# ai_cricket.net
KiCad netlist of a schematic drawn in EAGLE
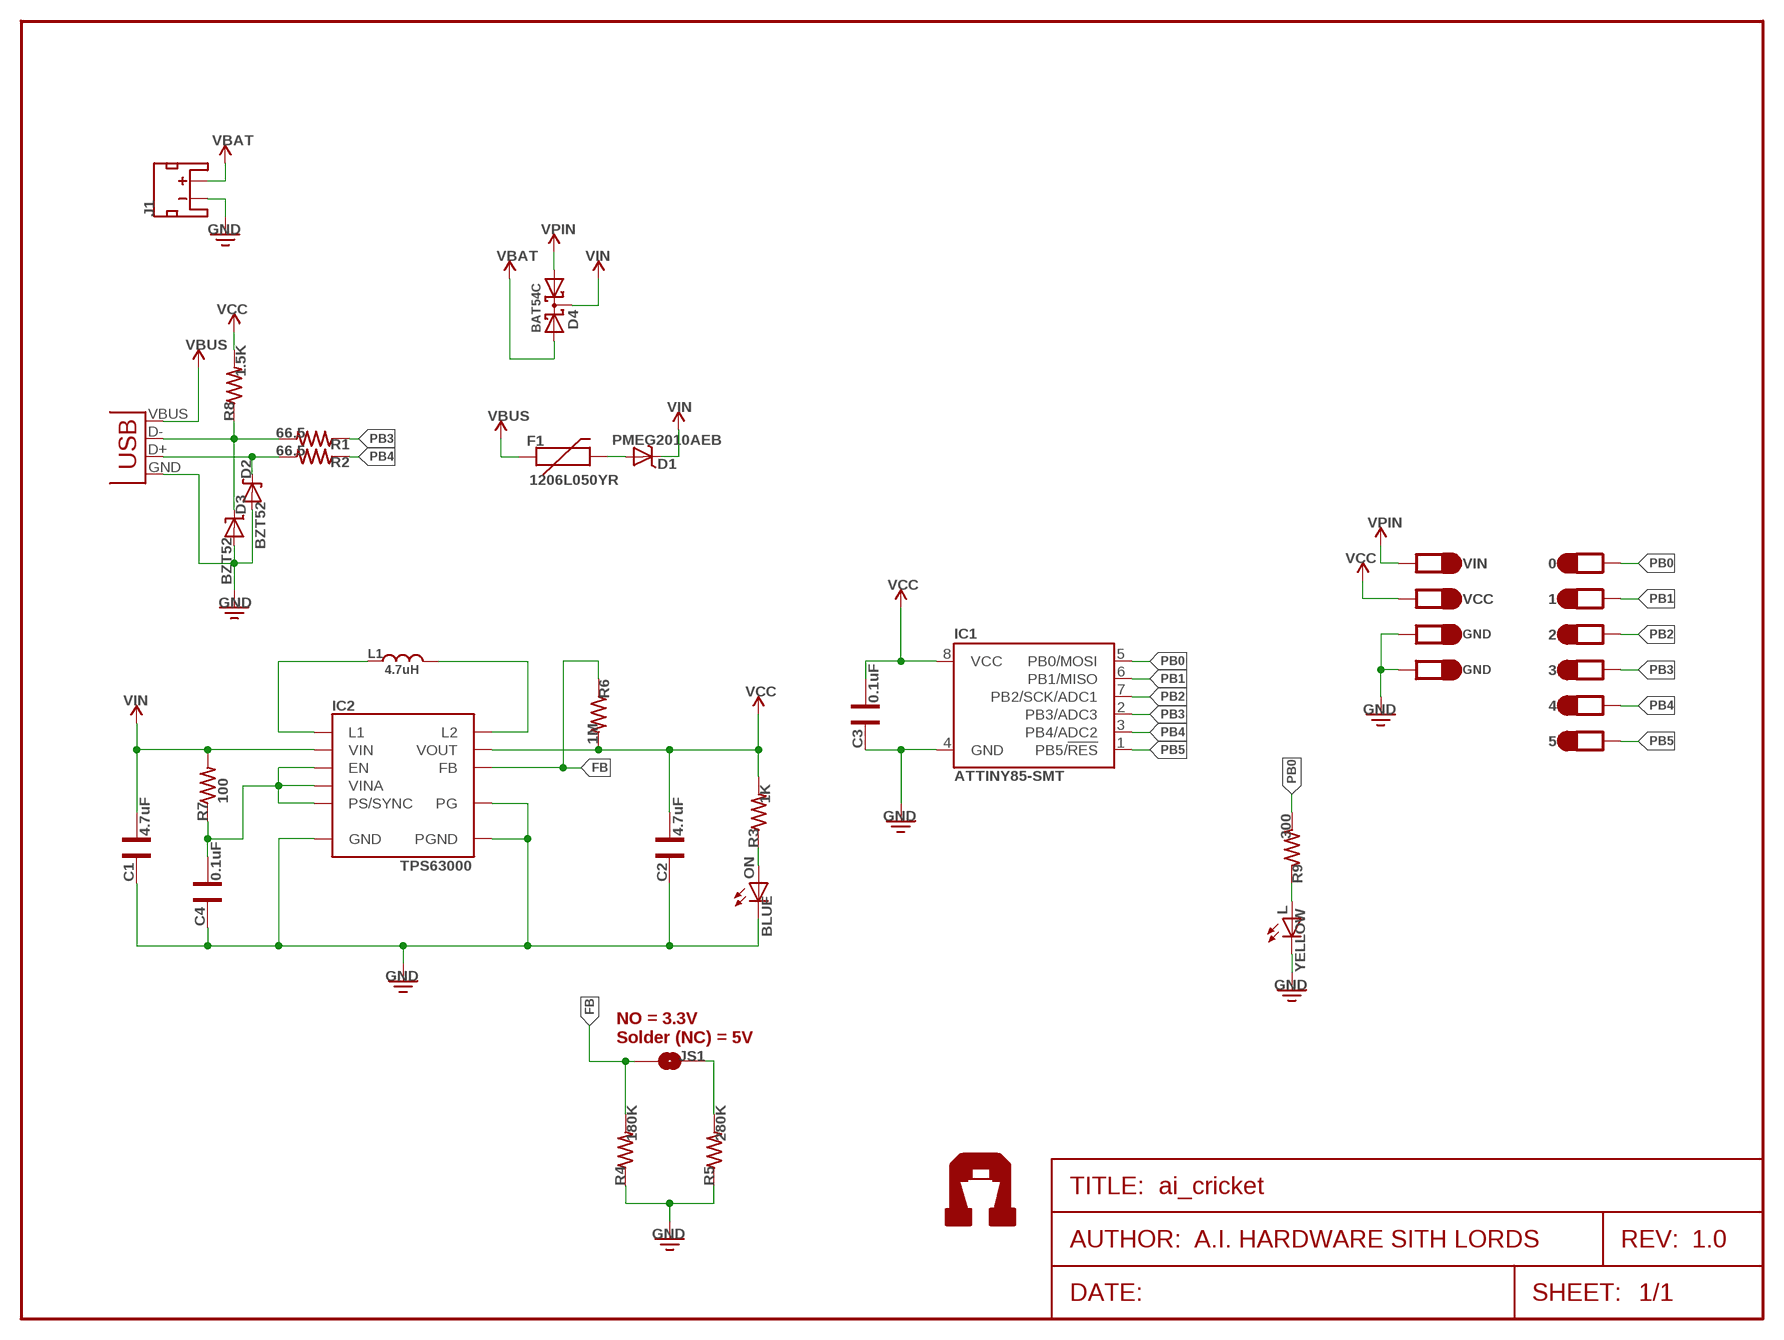
[diagram p0: schematic, sheet 1]

(export (version "E")
  (design (tool "Eeschema 10.0.6"))
  (components
    (comp (ref "0")
      (value "1X01-PETAL")
      (footprint "eagle-import:1X01-PETAL")
      (libsource (lib "eagle-import") (part "1X01-PETAL"))
    )
    (comp (ref "1")
      (value "1X01-PETAL")
      (footprint "eagle-import:1X01-PETAL")
      (libsource (lib "eagle-import") (part "1X01-PETAL"))
    )
    (comp (ref "2")
      (value "1X01-PETAL")
      (footprint "eagle-import:1X01-PETAL")
      (libsource (lib "eagle-import") (part "1X01-PETAL"))
    )
    (comp (ref "3")
      (value "1X01-PETAL")
      (footprint "eagle-import:1X01-PETAL")
      (libsource (lib "eagle-import") (part "1X01-PETAL"))
    )
    (comp (ref "4")
      (value "1X01-PETAL")
      (footprint "eagle-import:1X01-PETAL")
      (libsource (lib "eagle-import") (part "1X01-PETAL"))
    )
    (comp (ref "5")
      (value "1X01-PETAL")
      (footprint "eagle-import:1X01-PETAL")
      (libsource (lib "eagle-import") (part "1X01-PETAL"))
    )
    (comp (ref "C1")
      (value "4.7uF")
      (footprint "eagle-import:CAP-0402")
      (libsource (lib "eagle-import") (part "CAP0402"))
    )
    (comp (ref "C2")
      (value "4.7uF")
      (footprint "eagle-import:CAP-0402")
      (libsource (lib "eagle-import") (part "CAP0402"))
    )
    (comp (ref "C3")
      (value "0.1uF")
      (footprint "eagle-import:CAP-0402")
      (libsource (lib "eagle-import") (part "CAP0402"))
    )
    (comp (ref "C4")
      (value "0.1uF")
      (footprint "eagle-import:CAP-0402")
      (libsource (lib "eagle-import") (part "CAP0402"))
    )
    (comp (ref "D1")
      (value "PMEG2010AEB")
      (footprint "eagle-import:SOD-523")
      (libsource (lib "eagle-import") (part "DIODE-SCHOTTKYSOD-523"))
    )
    (comp (ref "D2")
      (value "BZT52")
      (footprint "eagle-import:SOD-323")
      (libsource (lib "eagle-import") (part "DIODE-ZENER-BZT52"))
    )
    (comp (ref "D3")
      (value "BZT52")
      (footprint "eagle-import:SOD-323")
      (libsource (lib "eagle-import") (part "DIODE-ZENER-BZT52"))
    )
    (comp (ref "D4")
      (value "BAT54C")
      (footprint "eagle-import:SOT-23")
      (libsource (lib "eagle-import") (part "BAT54C"))
    )
    (comp (ref "F1")
      (value "1206L050YR")
      (footprint "eagle-import:PTC-1206")
      (libsource (lib "eagle-import") (part "PTCSMD"))
    )
    (comp (ref "GND7")
      (value "1X01-PETAL")
      (footprint "eagle-import:1X01-PETAL")
      (libsource (lib "eagle-import") (part "1X01-PETAL"))
    )
    (comp (ref "GND8")
      (value "1X01-PETAL")
      (footprint "eagle-import:1X01-PETAL")
      (libsource (lib "eagle-import") (part "1X01-PETAL"))
    )
    (comp (ref "IC1")
      (value "ATTINY85-SMT")
      (footprint "eagle-import:S008-EIAJ")
      (libsource (lib "eagle-import") (part "ATTINY85-SMT"))
    )
    (comp (ref "IC2")
      (value "TPS63000")
      (footprint "eagle-import:10-VFDFN")
      (libsource (lib "eagle-import") (part "TPS63000"))
    )
    (comp (ref "J1")
      (value "JST-2-MALE")
      (footprint "eagle-import:JST-2-SMD")
      (libsource (lib "eagle-import") (part "JST-2-MALE"))
    )
    (comp (ref "JS1")
      (value "1X02-SJ-NO")
      (footprint "eagle-import:1X02-SJ-NO")
      (libsource (lib "eagle-import") (part "1X02-SJ-NO"))
    )
    (comp (ref "L")
      (value "YELLOW")
      (footprint "eagle-import:LED-0603")
      (libsource (lib "eagle-import") (part "LED0603"))
    )
    (comp (ref "L1")
      (value "4.7uH")
      (footprint "eagle-import:IND-0603")
      (libsource (lib "eagle-import") (part "IND0603"))
    )
    (comp (ref "ON")
      (value "BLUE")
      (footprint "eagle-import:LED-0603")
      (libsource (lib "eagle-import") (part "LED0603"))
    )
    (comp (ref "R1")
      (value "66.5")
      (footprint "eagle-import:RES-0402")
      (libsource (lib "eagle-import") (part "RES0402"))
    )
    (comp (ref "R2")
      (value "66.5")
      (footprint "eagle-import:RES-0402")
      (libsource (lib "eagle-import") (part "RES0402"))
    )
    (comp (ref "R3")
      (value "1K")
      (footprint "eagle-import:RES-0402")
      (libsource (lib "eagle-import") (part "RES0402"))
    )
    (comp (ref "R4")
      (value "180K")
      (footprint "eagle-import:RES-0402")
      (libsource (lib "eagle-import") (part "RES0402"))
    )
    (comp (ref "R5")
      (value "280K")
      (footprint "eagle-import:RES-0402")
      (libsource (lib "eagle-import") (part "RES0402"))
    )
    (comp (ref "R6")
      (value "1M")
      (footprint "eagle-import:RES-0402")
      (libsource (lib "eagle-import") (part "RES0402"))
    )
    (comp (ref "R7")
      (value "100")
      (footprint "eagle-import:RES-0402")
      (libsource (lib "eagle-import") (part "RES0402"))
    )
    (comp (ref "R8")
      (value "1.5K")
      (footprint "eagle-import:RES-0402")
      (libsource (lib "eagle-import") (part "RES0402"))
    )
    (comp (ref "R9")
      (value "300")
      (footprint "eagle-import:RES-0402")
      (libsource (lib "eagle-import") (part "RES0402"))
    )
    (comp (ref "U$14")
      (value "AI-LOGOXS")
      (footprint "eagle-import:AI-LOGO-XS")
      (libsource (lib "eagle-import") (part "AI-LOGOXS"))
    )
    (comp (ref "USB1")
      (value "USBMICROB-TH")
      (footprint "eagle-import:USB-MICROB-TH")
      (libsource (lib "eagle-import") (part "USBMICROB-TH"))
    )
    (comp (ref "VCC")
      (value "1X01-PETAL")
      (footprint "eagle-import:1X01-PETAL")
      (libsource (lib "eagle-import") (part "1X01-PETAL"))
    )
    (comp (ref "VIN")
      (value "1X01-PETAL")
      (footprint "eagle-import:1X01-PETAL")
      (libsource (lib "eagle-import") (part "1X01-PETAL"))
    )
  )
  (nets
    (net (code "1") (name "FB") (class "Default")
      (node (ref "IC2") (pin "10") (pinfunction "FB_10") (pintype "input"))
      (node (ref "JS1") (pin "1") (pinfunction "1_1") (pintype "passive"))
      (node (ref "R4") (pin "2") (pinfunction "2_2") (pintype "passive"))
      (node (ref "R6") (pin "1") (pinfunction "1_1") (pintype "passive"))
    )
    (net (code "2") (name "GND") (class "Default")
      (node (ref "C1") (pin "2") (pinfunction "2_2") (pintype "passive"))
      (node (ref "C2") (pin "2") (pinfunction "2_2") (pintype "passive"))
      (node (ref "C3") (pin "2") (pinfunction "2_2") (pintype "passive"))
      (node (ref "C4") (pin "2") (pinfunction "2_2") (pintype "passive"))
      (node (ref "D2") (pin "A") (pinfunction "A_A") (pintype "passive"))
      (node (ref "D3") (pin "A") (pinfunction "A_A") (pintype "passive"))
      (node (ref "GND7") (pin "1") (pinfunction "1_1") (pintype "bidirectional"))
      (node (ref "GND8") (pin "1") (pinfunction "1_1") (pintype "bidirectional"))
      (node (ref "IC1") (pin "4") (pinfunction "GND_4") (pintype "bidirectional"))
      (node (ref "IC2") (pin "3") (pinfunction "PGND_3") (pintype "power_in"))
      (node (ref "IC2") (pin "9") (pinfunction "GND_9") (pintype "power_in"))
      (node (ref "IC2") (pin "P$1") (pinfunction "PG_P$1") (pintype "power_in"))
      (node (ref "IC2") (pin "P$2") (pinfunction "PG_P$2") (pintype "power_in"))
      (node (ref "IC2") (pin "P$3") (pinfunction "PG_P$3") (pintype "power_in"))
      (node (ref "IC2") (pin "P$4") (pinfunction "PG_P$4") (pintype "power_in"))
      (node (ref "IC2") (pin "P$5") (pinfunction "PG_P$5") (pintype "power_in"))
      (node (ref "J1") (pin "2") (pinfunction "-_2") (pintype "power_in"))
      (node (ref "L") (pin "C") (pinfunction "C_C") (pintype "passive"))
      (node (ref "ON") (pin "C") (pinfunction "C_C") (pintype "passive"))
      (node (ref "R4") (pin "1") (pinfunction "1_1") (pintype "passive"))
      (node (ref "R5") (pin "1") (pinfunction "1_1") (pintype "passive"))
      (node (ref "USB1") (pin "GND") (pinfunction "GND_GND") (pintype "bidirectional"))
    )
    (net (code "3") (name "Net-(D1-PadA)") (class "Default")
      (node (ref "D1") (pin "A") (pinfunction "A_A") (pintype "passive"))
      (node (ref "F1") (pin "2") (pinfunction "2_2") (pintype "bidirectional"))
    )
    (net (code "4") (name "Net-(D2-PadC)") (class "Default")
      (node (ref "D2") (pin "C") (pinfunction "C_C") (pintype "passive"))
      (node (ref "R2") (pin "2") (pinfunction "2_2") (pintype "passive"))
      (node (ref "USB1") (pin "D+") (pinfunction "D+_D+") (pintype "bidirectional"))
    )
    (net (code "5") (name "Net-(D3-PadC)") (class "Default")
      (node (ref "D3") (pin "C") (pinfunction "C_C") (pintype "passive"))
      (node (ref "R1") (pin "2") (pinfunction "2_2") (pintype "passive"))
      (node (ref "R8") (pin "1") (pinfunction "1_1") (pintype "passive"))
      (node (ref "USB1") (pin "D-") (pinfunction "D-_D-") (pintype "bidirectional"))
    )
    (net (code "6") (name "Net-(IC2-EN)") (class "Default")
      (node (ref "C4") (pin "1") (pinfunction "1_1") (pintype "passive"))
      (node (ref "IC2") (pin "6") (pinfunction "EN_6") (pintype "bidirectional"))
      (node (ref "IC2") (pin "7") (pinfunction "PS/SYNC_7") (pintype "input"))
      (node (ref "IC2") (pin "8") (pinfunction "VINA_8") (pintype "power_in"))
      (node (ref "R7") (pin "1") (pinfunction "1_1") (pintype "passive"))
    )
    (net (code "7") (name "Net-(IC2-L1)") (class "Default")
      (node (ref "IC2") (pin "4") (pinfunction "L1_4") (pintype "passive"))
      (node (ref "L1") (pin "2") (pinfunction "2_2") (pintype "passive"))
    )
    (net (code "8") (name "Net-(IC2-L2)") (class "Default")
      (node (ref "IC2") (pin "2") (pinfunction "L2_2") (pintype "passive"))
      (node (ref "L1") (pin "1") (pinfunction "1_1") (pintype "passive"))
    )
    (net (code "9") (name "Net-(JS1-Pad2)") (class "Default")
      (node (ref "JS1") (pin "2") (pinfunction "2_2") (pintype "passive"))
      (node (ref "R5") (pin "2") (pinfunction "2_2") (pintype "passive"))
    )
    (net (code "10") (name "Net-(L-PadA)") (class "Default")
      (node (ref "L") (pin "A") (pinfunction "A_A") (pintype "passive"))
      (node (ref "R9") (pin "1") (pinfunction "1_1") (pintype "passive"))
    )
    (net (code "11") (name "Net-(ON-PadA)") (class "Default")
      (node (ref "ON") (pin "A") (pinfunction "A_A") (pintype "passive"))
      (node (ref "R3") (pin "1") (pinfunction "1_1") (pintype "passive"))
    )
    (net (code "12") (name "PB0") (class "Default")
      (node (ref "0") (pin "1") (pinfunction "1_1") (pintype "bidirectional"))
      (node (ref "IC1") (pin "5") (pinfunction "PB0/MOSI_5") (pintype "bidirectional"))
      (node (ref "R9") (pin "2") (pinfunction "2_2") (pintype "passive"))
    )
    (net (code "13") (name "PB1") (class "Default")
      (node (ref "1") (pin "1") (pinfunction "1_1") (pintype "bidirectional"))
      (node (ref "IC1") (pin "6") (pinfunction "PB1/MISO_6") (pintype "bidirectional"))
    )
    (net (code "14") (name "PB2") (class "Default")
      (node (ref "2") (pin "1") (pinfunction "1_1") (pintype "bidirectional"))
      (node (ref "IC1") (pin "7") (pinfunction "PB2/SCK/ADC1_7") (pintype "bidirectional"))
    )
    (net (code "15") (name "PB3") (class "Default")
      (node (ref "3") (pin "1") (pinfunction "1_1") (pintype "bidirectional"))
      (node (ref "IC1") (pin "2") (pinfunction "PB3/ADC3_2") (pintype "bidirectional"))
      (node (ref "R1") (pin "1") (pinfunction "1_1") (pintype "passive"))
    )
    (net (code "16") (name "PB4") (class "Default")
      (node (ref "4") (pin "1") (pinfunction "1_1") (pintype "bidirectional"))
      (node (ref "IC1") (pin "3") (pinfunction "PB4/ADC2_3") (pintype "bidirectional"))
      (node (ref "R2") (pin "1") (pinfunction "1_1") (pintype "passive"))
    )
    (net (code "17") (name "PB5") (class "Default")
      (node (ref "5") (pin "1") (pinfunction "1_1") (pintype "bidirectional"))
      (node (ref "IC1") (pin "1") (pinfunction "PB5/~{RES}_1") (pintype "bidirectional"))
    )
    (net (code "18") (name "VBAT") (class "Default")
      (node (ref "D4") (pin "2") (pinfunction "A2_2") (pintype "passive"))
      (node (ref "J1") (pin "1") (pinfunction "+_1") (pintype "power_in"))
    )
    (net (code "19") (name "VBUS") (class "Default")
      (node (ref "F1") (pin "1") (pinfunction "1_1") (pintype "bidirectional"))
      (node (ref "USB1") (pin "VBUS") (pinfunction "VBUS_VBUS") (pintype "bidirectional"))
    )
    (net (code "20") (name "VCC") (class "Default")
      (node (ref "C2") (pin "1") (pinfunction "1_1") (pintype "passive"))
      (node (ref "C3") (pin "1") (pinfunction "1_1") (pintype "passive"))
      (node (ref "IC1") (pin "8") (pinfunction "VCC_8") (pintype "bidirectional"))
      (node (ref "IC2") (pin "1") (pinfunction "VOUT_1") (pintype "power_in"))
      (node (ref "R3") (pin "2") (pinfunction "2_2") (pintype "passive"))
      (node (ref "R6") (pin "2") (pinfunction "2_2") (pintype "passive"))
      (node (ref "R8") (pin "2") (pinfunction "2_2") (pintype "passive"))
      (node (ref "VCC") (pin "1") (pinfunction "1_1") (pintype "bidirectional"))
    )
    (net (code "21") (name "VIN") (class "Default")
      (node (ref "C1") (pin "1") (pinfunction "1_1") (pintype "passive"))
      (node (ref "D1") (pin "C") (pinfunction "C_C") (pintype "passive"))
      (node (ref "D4") (pin "3") (pinfunction "CC_3") (pintype "passive"))
      (node (ref "IC2") (pin "5") (pinfunction "VIN_5") (pintype "power_in"))
      (node (ref "R7") (pin "2") (pinfunction "2_2") (pintype "passive"))
    )
    (net (code "22") (name "VPIN") (class "Default")
      (node (ref "D4") (pin "1") (pinfunction "A1_1") (pintype "passive"))
      (node (ref "VIN") (pin "1") (pinfunction "1_1") (pintype "bidirectional"))
    )
  )
)
